# proy_10A_SCH_1_v1i1.net
KiCad netlist of a schematic drawn in Altium Designer
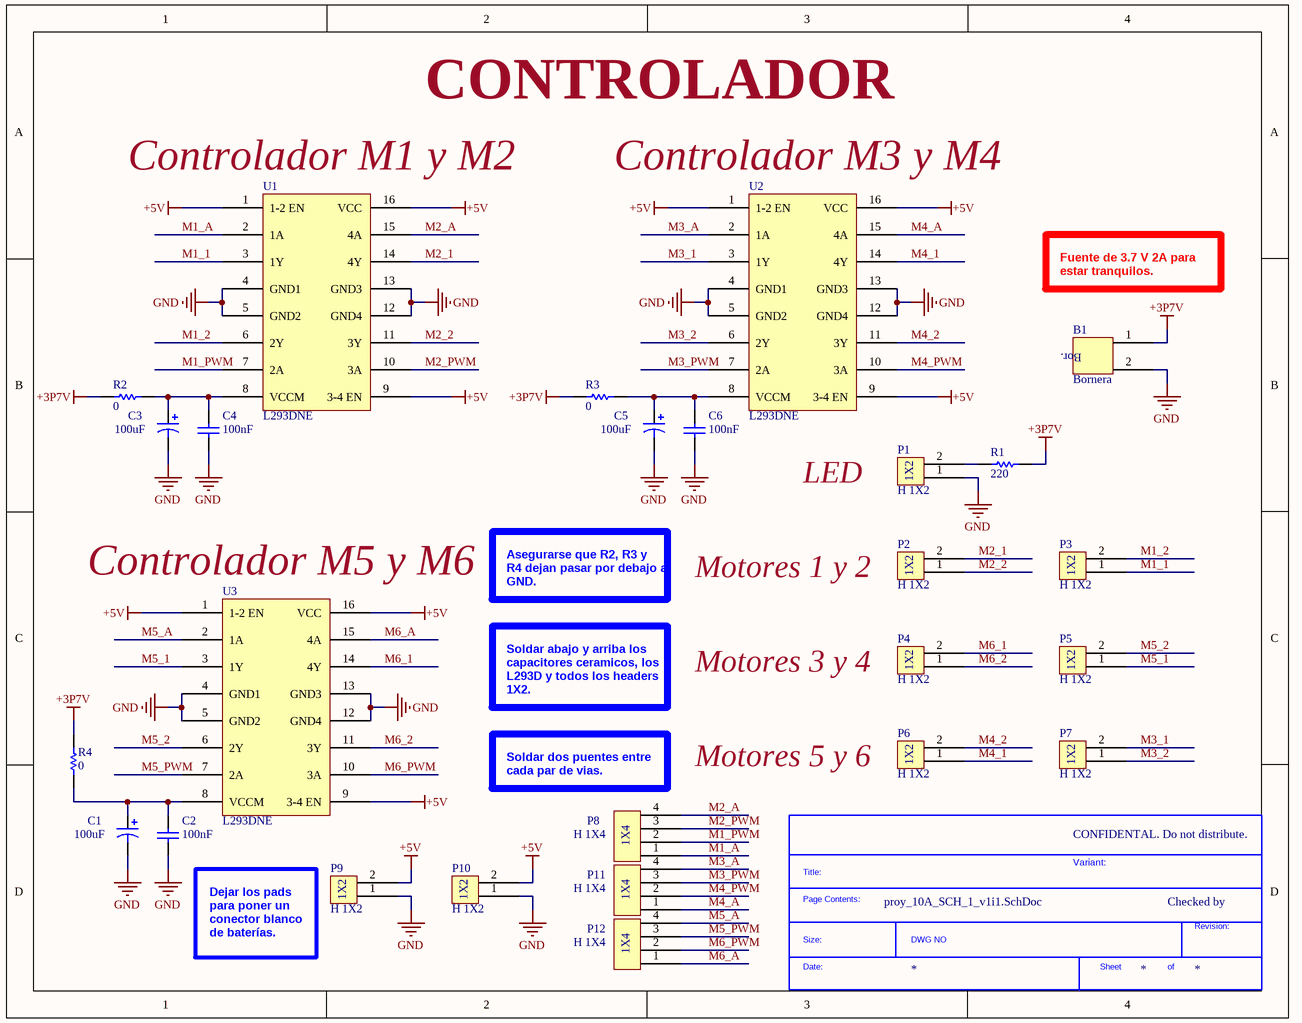
[diagram p0: proy_10A_SCH_1_v1i1.SchDoc]

(export (version "E")
  (design (tool "Eeschema 10.0.6"))
  (components
    (comp (ref "*") (value "SDTitleBlock") (libsource (lib "*") (part "SDTitleBlock")))
    (comp (ref "B1")
      (value "Bornera")
      (footprint "Bornera")
      (description "Bornera de 2 terminales.")
      (fields (field (name ".CREATOR") "SR"))
      (libsource (lib "Libreria_Santi") (part "Bornera"))
    )
    (comp (ref "C1")
      (value "100uF")
      (footprint "C 6.3x11")
      (description "Capacitor polarizado.")
      (fields (field (name ".CREATOR") "SR"))
      (libsource (lib "Libreria_Santi") (part "C POL"))
    )
    (comp (ref "C2")
      (value "100nF")
      (footprint "C Lenteja")
      (description "Capacitor")
      (fields (field (name ".CREATOR") "SR"))
      (libsource (lib "Libreria_Santi") (part "C"))
    )
    (comp (ref "C3")
      (value "100uF")
      (footprint "C 6.3x11")
      (description "Capacitor polarizado.")
      (fields (field (name ".CREATOR") "SR"))
      (libsource (lib "Libreria_Santi") (part "C POL"))
    )
    (comp (ref "C4")
      (value "100nF")
      (footprint "C Lenteja")
      (description "Capacitor")
      (fields (field (name ".CREATOR") "SR"))
      (libsource (lib "Libreria_Santi") (part "C"))
    )
    (comp (ref "C5")
      (value "100uF")
      (footprint "C 6.3x11")
      (description "Capacitor polarizado.")
      (fields (field (name ".CREATOR") "SR"))
      (libsource (lib "Libreria_Santi") (part "C POL"))
    )
    (comp (ref "C6")
      (value "100nF")
      (footprint "C Lenteja")
      (description "Capacitor")
      (fields (field (name ".CREATOR") "SR"))
      (libsource (lib "Libreria_Santi") (part "C"))
    )
    (comp (ref "P1")
      (value "H 1X2")
      (footprint "H 1x2")
      (description "PIN HEADER 1X2")
      (fields (field (name ".CREATOR") "SR"))
      (libsource (lib "Libreria_Santi") (part "H 1X2"))
    )
    (comp (ref "P2")
      (value "H 1X2")
      (footprint "H 1x2")
      (description "PIN HEADER 1X2")
      (fields (field (name ".CREATOR") "SR"))
      (libsource (lib "Libreria_Santi") (part "H 1X2"))
    )
    (comp (ref "P3")
      (value "H 1X2")
      (footprint "H 1x2")
      (description "PIN HEADER 1X2")
      (fields (field (name ".CREATOR") "SR"))
      (libsource (lib "Libreria_Santi") (part "H 1X2"))
    )
    (comp (ref "P4")
      (value "H 1X2")
      (footprint "H 1x2")
      (description "PIN HEADER 1X2")
      (fields (field (name ".CREATOR") "SR"))
      (libsource (lib "Libreria_Santi") (part "H 1X2"))
    )
    (comp (ref "P5")
      (value "H 1X2")
      (footprint "H 1x2")
      (description "PIN HEADER 1X2")
      (fields (field (name ".CREATOR") "SR"))
      (libsource (lib "Libreria_Santi") (part "H 1X2"))
    )
    (comp (ref "P6")
      (value "H 1X2")
      (footprint "H 1x2")
      (description "PIN HEADER 1X2")
      (fields (field (name ".CREATOR") "SR"))
      (libsource (lib "Libreria_Santi") (part "H 1X2"))
    )
    (comp (ref "P7")
      (value "H 1X2")
      (footprint "H 1x2")
      (description "PIN HEADER 1X2")
      (fields (field (name ".CREATOR") "SR"))
      (libsource (lib "Libreria_Santi") (part "H 1X2"))
    )
    (comp (ref "P8")
      (value "H 1X4")
      (footprint "H 1X4 - Hembra")
      (description "PIN HEADER 1X4")
      (fields (field (name ".CREATOR") "SR"))
      (libsource (lib "Libreria_Santi") (part "H 1X4"))
    )
    (comp (ref "P9")
      (value "H 1X2")
      (footprint "H 1x2")
      (description "PIN HEADER 1X2")
      (fields (field (name ".CREATOR") "SR"))
      (libsource (lib "Libreria_Santi") (part "H 1X2"))
    )
    (comp (ref "P10")
      (value "H 1X2")
      (footprint "H 1x2")
      (description "PIN HEADER 1X2")
      (fields (field (name ".CREATOR") "SR"))
      (libsource (lib "Libreria_Santi") (part "H 1X2"))
    )
    (comp (ref "P11")
      (value "H 1X4")
      (footprint "H 1X4 - Hembra")
      (description "PIN HEADER 1X4")
      (fields (field (name ".CREATOR") "SR"))
      (libsource (lib "Libreria_Santi") (part "H 1X4"))
    )
    (comp (ref "P12")
      (value "H 1X4")
      (footprint "H 1X4 - Hembra")
      (description "PIN HEADER 1X4")
      (fields (field (name ".CREATOR") "SR"))
      (libsource (lib "Libreria_Santi") (part "H 1X4"))
    )
    (comp (ref "R1")
      (value "220")
      (footprint "R 1206")
      (description "Resistencia")
      (fields (field (name ".CREATOR") "SR"))
      (libsource (lib "Libreria_Santi") (part "R"))
    )
    (comp (ref "R2")
      (value "0")
      (footprint "R 1206")
      (description "Resistencia")
      (fields (field (name ".CREATOR") "SR"))
      (libsource (lib "Libreria_Santi") (part "R"))
    )
    (comp (ref "R3")
      (value "0")
      (footprint "R 1206")
      (description "Resistencia")
      (fields (field (name ".CREATOR") "SR"))
      (libsource (lib "Libreria_Santi") (part "R"))
    )
    (comp (ref "R4")
      (value "0")
      (footprint "R 1206")
      (description "Resistencia")
      (fields (field (name ".CREATOR") "SR"))
      (libsource (lib "Libreria_Santi") (part "R"))
    )
    (comp (ref "U1")
      (value "L293DNE")
      (footprint "DIP-16")
      (description "IC MOTOR DRIVER PAR 16-DIP")
      (fields
        (field (name "MANUFACTURER") "Texas Instruments")
        (field (name ".CREATOR") "SR")
        (field (name ".PCBCHECK") "SR")
        (field (name ".SCHCHECK") "SR")
      )
      (libsource (lib "Libreria_Santi") (part "L293DNE"))
    )
    (comp (ref "U2")
      (value "L293DNE")
      (footprint "DIP-16")
      (description "IC MOTOR DRIVER PAR 16-DIP")
      (fields
        (field (name "MANUFACTURER") "Texas Instruments")
        (field (name ".CREATOR") "SR")
        (field (name ".PCBCHECK") "SR")
        (field (name ".SCHCHECK") "SR")
      )
      (libsource (lib "Libreria_Santi") (part "L293DNE"))
    )
    (comp (ref "U3")
      (value "L293DNE")
      (footprint "DIP-16")
      (description "IC MOTOR DRIVER PAR 16-DIP")
      (fields
        (field (name "MANUFACTURER") "Texas Instruments")
        (field (name ".CREATOR") "SR")
        (field (name ".PCBCHECK") "SR")
        (field (name ".SCHCHECK") "SR")
      )
      (libsource (lib "Libreria_Santi") (part "L293DNE"))
    )
  )
  (nets
    (net (code "1") (name "+3P7V") (class "Default")
      (node (ref "B1") (pin "1") (pinfunction "1_1") (pintype "passive"))
      (node (ref "R1") (pin "2") (pinfunction "2_2") (pintype "passive"))
      (node (ref "R2") (pin "1") (pinfunction "1_1") (pintype "passive"))
      (node (ref "R3") (pin "1") (pinfunction "1_1") (pintype "passive"))
      (node (ref "R4") (pin "1") (pinfunction "1_1") (pintype "passive"))
    )
    (net (code "2") (name "+5V") (class "Default")
      (node (ref "P10") (pin "2") (pinfunction "2_2") (pintype "passive"))
      (node (ref "P9") (pin "2") (pinfunction "2_2") (pintype "passive"))
      (node (ref "U1") (pin "1") (pinfunction "1-2_EN_1") (pintype "passive"))
      (node (ref "U1") (pin "16") (pinfunction "VCC_16") (pintype "passive"))
      (node (ref "U1") (pin "9") (pinfunction "3-4_EN_9") (pintype "passive"))
      (node (ref "U2") (pin "1") (pinfunction "1-2_EN_1") (pintype "passive"))
      (node (ref "U2") (pin "16") (pinfunction "VCC_16") (pintype "passive"))
      (node (ref "U2") (pin "9") (pinfunction "3-4_EN_9") (pintype "passive"))
      (node (ref "U3") (pin "1") (pinfunction "1-2_EN_1") (pintype "passive"))
      (node (ref "U3") (pin "16") (pinfunction "VCC_16") (pintype "passive"))
      (node (ref "U3") (pin "9") (pinfunction "3-4_EN_9") (pintype "passive"))
    )
    (net (code "3") (name "/M1_1") (class "Default")
      (node (ref "P3") (pin "1") (pinfunction "1_1") (pintype "passive"))
      (node (ref "U1") (pin "3") (pinfunction "1Y_3") (pintype "passive"))
    )
    (net (code "4") (name "/M1_2") (class "Default")
      (node (ref "P3") (pin "2") (pinfunction "2_2") (pintype "passive"))
      (node (ref "U1") (pin "6") (pinfunction "2Y_6") (pintype "passive"))
    )
    (net (code "5") (name "/M1_A") (class "Default")
      (node (ref "P8") (pin "1") (pinfunction "1_1") (pintype "passive"))
      (node (ref "U1") (pin "2") (pinfunction "1A_2") (pintype "passive"))
    )
    (net (code "6") (name "/M1_PWM") (class "Default")
      (node (ref "P8") (pin "2") (pinfunction "2_2") (pintype "passive"))
      (node (ref "U1") (pin "7") (pinfunction "2A_7") (pintype "passive"))
    )
    (net (code "7") (name "/M2_1") (class "Default")
      (node (ref "P2") (pin "2") (pinfunction "2_2") (pintype "passive"))
      (node (ref "U1") (pin "14") (pinfunction "4Y_14") (pintype "passive"))
    )
    (net (code "8") (name "/M2_2") (class "Default")
      (node (ref "P2") (pin "1") (pinfunction "1_1") (pintype "passive"))
      (node (ref "U1") (pin "11") (pinfunction "3Y_11") (pintype "passive"))
    )
    (net (code "9") (name "/M2_A") (class "Default")
      (node (ref "P8") (pin "4") (pinfunction "4_4") (pintype "passive"))
      (node (ref "U1") (pin "15") (pinfunction "4A_15") (pintype "passive"))
    )
    (net (code "10") (name "/M2_PWM") (class "Default")
      (node (ref "P8") (pin "3") (pinfunction "3_3") (pintype "passive"))
      (node (ref "U1") (pin "10") (pinfunction "3A_10") (pintype "passive"))
    )
    (net (code "11") (name "/M3_1") (class "Default")
      (node (ref "P7") (pin "2") (pinfunction "2_2") (pintype "passive"))
      (node (ref "U2") (pin "3") (pinfunction "1Y_3") (pintype "passive"))
    )
    (net (code "12") (name "/M3_2") (class "Default")
      (node (ref "P7") (pin "1") (pinfunction "1_1") (pintype "passive"))
      (node (ref "U2") (pin "6") (pinfunction "2Y_6") (pintype "passive"))
    )
    (net (code "13") (name "/M3_A") (class "Default")
      (node (ref "P11") (pin "4") (pinfunction "4_4") (pintype "passive"))
      (node (ref "U2") (pin "2") (pinfunction "1A_2") (pintype "passive"))
    )
    (net (code "14") (name "/M3_PWM") (class "Default")
      (node (ref "P11") (pin "3") (pinfunction "3_3") (pintype "passive"))
      (node (ref "U2") (pin "7") (pinfunction "2A_7") (pintype "passive"))
    )
    (net (code "15") (name "/M4_1") (class "Default")
      (node (ref "P6") (pin "1") (pinfunction "1_1") (pintype "passive"))
      (node (ref "U2") (pin "14") (pinfunction "4Y_14") (pintype "passive"))
    )
    (net (code "16") (name "/M4_2") (class "Default")
      (node (ref "P6") (pin "2") (pinfunction "2_2") (pintype "passive"))
      (node (ref "U2") (pin "11") (pinfunction "3Y_11") (pintype "passive"))
    )
    (net (code "17") (name "/M4_A") (class "Default")
      (node (ref "P11") (pin "1") (pinfunction "1_1") (pintype "passive"))
      (node (ref "U2") (pin "15") (pinfunction "4A_15") (pintype "passive"))
    )
    (net (code "18") (name "/M4_PWM") (class "Default")
      (node (ref "P11") (pin "2") (pinfunction "2_2") (pintype "passive"))
      (node (ref "U2") (pin "10") (pinfunction "3A_10") (pintype "passive"))
    )
    (net (code "19") (name "/M5_1") (class "Default")
      (node (ref "P5") (pin "1") (pinfunction "1_1") (pintype "passive"))
      (node (ref "U3") (pin "3") (pinfunction "1Y_3") (pintype "passive"))
    )
    (net (code "20") (name "/M5_2") (class "Default")
      (node (ref "P5") (pin "2") (pinfunction "2_2") (pintype "passive"))
      (node (ref "U3") (pin "6") (pinfunction "2Y_6") (pintype "passive"))
    )
    (net (code "21") (name "/M5_A") (class "Default")
      (node (ref "P12") (pin "4") (pinfunction "4_4") (pintype "passive"))
      (node (ref "U3") (pin "2") (pinfunction "1A_2") (pintype "passive"))
    )
    (net (code "22") (name "/M5_PWM") (class "Default")
      (node (ref "P12") (pin "3") (pinfunction "3_3") (pintype "passive"))
      (node (ref "U3") (pin "7") (pinfunction "2A_7") (pintype "passive"))
    )
    (net (code "23") (name "/M6_1") (class "Default")
      (node (ref "P4") (pin "2") (pinfunction "2_2") (pintype "passive"))
      (node (ref "U3") (pin "14") (pinfunction "4Y_14") (pintype "passive"))
    )
    (net (code "24") (name "/M6_2") (class "Default")
      (node (ref "P4") (pin "1") (pinfunction "1_1") (pintype "passive"))
      (node (ref "U3") (pin "11") (pinfunction "3Y_11") (pintype "passive"))
    )
    (net (code "25") (name "/M6_A") (class "Default")
      (node (ref "P12") (pin "1") (pinfunction "1_1") (pintype "passive"))
      (node (ref "U3") (pin "15") (pinfunction "4A_15") (pintype "passive"))
    )
    (net (code "26") (name "/M6_PWM") (class "Default")
      (node (ref "P12") (pin "2") (pinfunction "2_2") (pintype "passive"))
      (node (ref "U3") (pin "10") (pinfunction "3A_10") (pintype "passive"))
    )
    (net (code "27") (name "GND") (class "Default")
      (node (ref "B1") (pin "2") (pinfunction "2_2") (pintype "passive"))
      (node (ref "C1") (pin "2") (pinfunction "2_2") (pintype "passive"))
      (node (ref "C2") (pin "1") (pinfunction "1_1") (pintype "passive"))
      (node (ref "C3") (pin "2") (pinfunction "2_2") (pintype "passive"))
      (node (ref "C4") (pin "1") (pinfunction "1_1") (pintype "passive"))
      (node (ref "C5") (pin "2") (pinfunction "2_2") (pintype "passive"))
      (node (ref "C6") (pin "1") (pinfunction "1_1") (pintype "passive"))
      (node (ref "P1") (pin "1") (pinfunction "1_1") (pintype "passive"))
      (node (ref "P10") (pin "1") (pinfunction "1_1") (pintype "passive"))
      (node (ref "P9") (pin "1") (pinfunction "1_1") (pintype "passive"))
      (node (ref "U1") (pin "12") (pinfunction "GND4_12") (pintype "passive"))
      (node (ref "U1") (pin "13") (pinfunction "GND3_13") (pintype "passive"))
      (node (ref "U1") (pin "4") (pinfunction "GND1_4") (pintype "passive"))
      (node (ref "U1") (pin "5") (pinfunction "GND2_5") (pintype "passive"))
      (node (ref "U2") (pin "12") (pinfunction "GND4_12") (pintype "passive"))
      (node (ref "U2") (pin "13") (pinfunction "GND3_13") (pintype "passive"))
      (node (ref "U2") (pin "4") (pinfunction "GND1_4") (pintype "passive"))
      (node (ref "U2") (pin "5") (pinfunction "GND2_5") (pintype "passive"))
      (node (ref "U3") (pin "12") (pinfunction "GND4_12") (pintype "passive"))
      (node (ref "U3") (pin "13") (pinfunction "GND3_13") (pintype "passive"))
      (node (ref "U3") (pin "4") (pinfunction "GND1_4") (pintype "passive"))
      (node (ref "U3") (pin "5") (pinfunction "GND2_5") (pintype "passive"))
    )
    (net (code "28") (name "Net-(P1-Pad2)") (class "Default")
      (node (ref "P1") (pin "2") (pinfunction "2_2") (pintype "passive"))
      (node (ref "R1") (pin "1") (pinfunction "1_1") (pintype "passive"))
    )
    (net (code "29") (name "Net-(U1-VCCM)") (class "Default")
      (node (ref "C3") (pin "1") (pinfunction "1_1") (pintype "passive"))
      (node (ref "C4") (pin "2") (pinfunction "2_2") (pintype "passive"))
      (node (ref "R2") (pin "2") (pinfunction "2_2") (pintype "passive"))
      (node (ref "U1") (pin "8") (pinfunction "VCCM_8") (pintype "passive"))
    )
    (net (code "30") (name "Net-(U2-VCCM)") (class "Default")
      (node (ref "C5") (pin "1") (pinfunction "1_1") (pintype "passive"))
      (node (ref "C6") (pin "2") (pinfunction "2_2") (pintype "passive"))
      (node (ref "R3") (pin "2") (pinfunction "2_2") (pintype "passive"))
      (node (ref "U2") (pin "8") (pinfunction "VCCM_8") (pintype "passive"))
    )
    (net (code "31") (name "Net-(U3-VCCM)") (class "Default")
      (node (ref "C1") (pin "1") (pinfunction "1_1") (pintype "passive"))
      (node (ref "C2") (pin "2") (pinfunction "2_2") (pintype "passive"))
      (node (ref "R4") (pin "2") (pinfunction "2_2") (pintype "passive"))
      (node (ref "U3") (pin "8") (pinfunction "VCCM_8") (pintype "passive"))
    )
  )
)
